# Relay.net
KiCad netlist of a schematic drawn in EAGLE
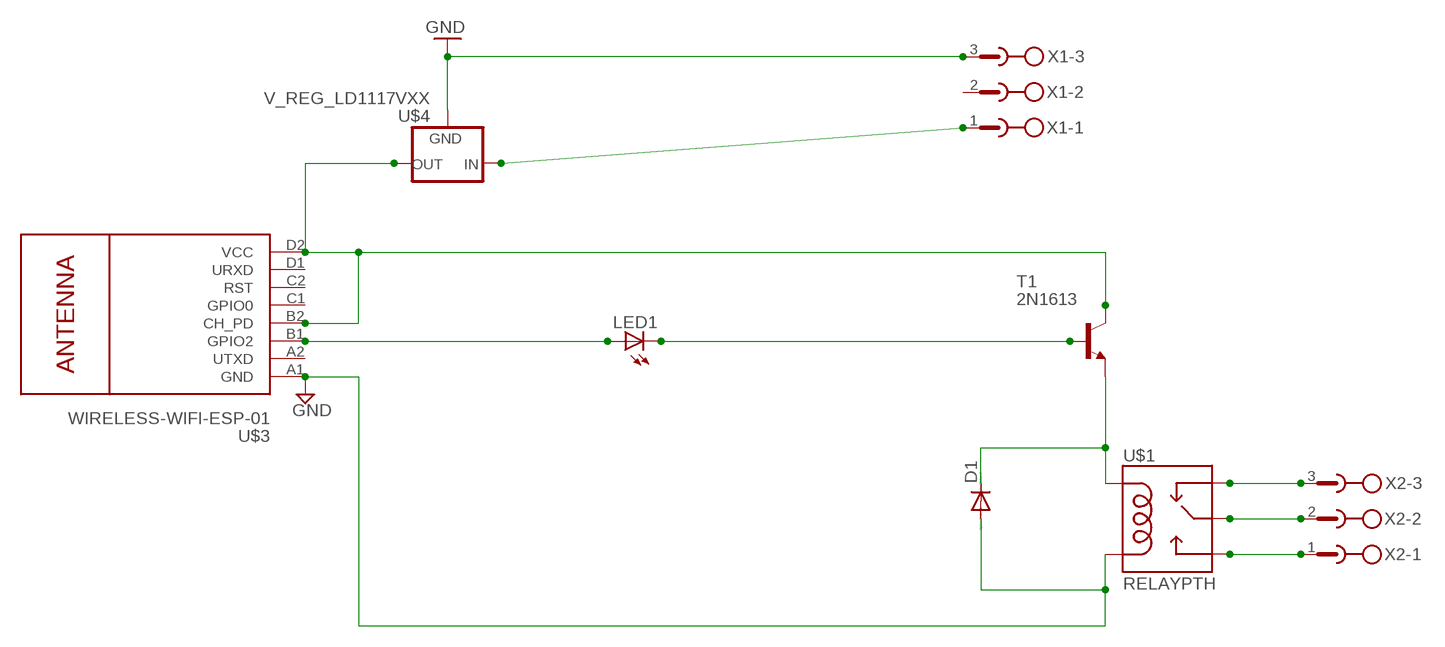
[diagram p0: schematic, sheet 1]

(export (version "E")
  (design (tool "Eeschema 10.0.6"))
  (components
    (comp (ref "D1")
      (value "DIODE-D-2.5")
      (footprint "eagle-import:D-2.5")
      (libsource (lib "eagle-import") (part "DIODE-D-2.5"))
    )
    (comp (ref "LED1")
      (value "LED3MM")
      (footprint "eagle-import:LED3MM")
      (libsource (lib "eagle-import") (part "LED3MM"))
    )
    (comp (ref "T1")
      (value "2N1613")
      (footprint "eagle-import:TO5")
      (libsource (lib "eagle-import") (part "2N1613"))
    )
    (comp (ref "U$1")
      (value "RELAYPTH")
      (footprint "eagle-import:SRD-05VDC-SL-C")
      (libsource (lib "eagle-import") (part "RELAYPTH"))
    )
    (comp (ref "U$3")
      (value "WIRELESS-WIFI-ESP-01")
      (footprint "eagle-import:WIRELESS-WIFI-ESP-01")
      (libsource (lib "eagle-import") (part "WIRELESS-WIFI-ESP-01"))
    )
    (comp (ref "U$4")
      (value "V_REG_LD1117VXX")
      (footprint "eagle-import:78XXL")
      (libsource (lib "eagle-import") (part "V_REG_LD1117VXX"))
    )
    (comp (ref "X1")
      (value "W232-3")
      (footprint "eagle-import:W232-3")
      (libsource (lib "eagle-import") (part "W232-3"))
    )
    (comp (ref "X2")
      (value "W232-3")
      (footprint "eagle-import:W232-3")
      (libsource (lib "eagle-import") (part "W232-3"))
    )
  )
  (nets
    (net (code "1") (name "GND") (class "Default")
      (node (ref "D1") (pin "A") (pinfunction "A_A") (pintype "passive"))
      (node (ref "U$1") (pin "COIL0") (pinfunction "COIL0_COIL0") (pintype "bidirectional"))
      (node (ref "U$3") (pin "A1") (pinfunction "GND_A1") (pintype "power_in"))
      (node (ref "U$4") (pin "IN") (pinfunction "GND_IN") (pintype "input"))
      (node (ref "X1") (pin "3") (pinfunction "SK_3") (pintype "passive"))
    )
    (net (code "2") (name "Net-(LED1-C)") (class "Default")
      (node (ref "LED1") (pin "K") (pinfunction "C_K") (pintype "passive"))
      (node (ref "T1") (pin "2") (pinfunction "B_2") (pintype "passive"))
    )
    (net (code "3") (name "Net-(T1-C)") (class "Default")
      (node (ref "T1") (pin "3") (pinfunction "C_3") (pintype "passive"))
      (node (ref "U$3") (pin "B2") (pinfunction "CH_PD_B2") (pintype "bidirectional"))
      (node (ref "U$3") (pin "D2") (pinfunction "VCC_D2") (pintype "power_in"))
      (node (ref "U$4") (pin "GND") (pinfunction "OUT_GND") (pintype "passive"))
    )
    (net (code "4") (name "Net-(T1-E)") (class "Default")
      (node (ref "D1") (pin "C") (pinfunction "C_C") (pintype "passive"))
      (node (ref "T1") (pin "1") (pinfunction "E_1") (pintype "passive"))
      (node (ref "U$1") (pin "COIL1") (pinfunction "COIL1_COIL1") (pintype "bidirectional"))
    )
    (net (code "5") (name "Net-(U$1-SWCLOSE)") (class "Default")
      (node (ref "U$1") (pin "SWCLOSED") (pinfunction "SWCLOSE_SWCLOSED") (pintype "bidirectional"))
      (node (ref "X2") (pin "3") (pinfunction "SK_3") (pintype "passive"))
    )
    (net (code "6") (name "Net-(U$3-GPIO2)") (class "Default")
      (node (ref "LED1") (pin "A") (pinfunction "A_A") (pintype "passive"))
      (node (ref "U$3") (pin "B1") (pinfunction "GPIO2_B1") (pintype "bidirectional"))
    )
    (net (code "7") (name "Net-(U$4-IN)") (class "Default")
      (node (ref "U$4") (pin "OUT") (pinfunction "IN_OUT") (pintype "input"))
      (node (ref "X1") (pin "1") (pinfunction "SK_1") (pintype "passive"))
    )
    (net (code "8") (name "Net-(X2A-SK)") (class "Default")
      (node (ref "U$1") (pin "SWOPEN") (pinfunction "SWOPEN_SWOPEN") (pintype "bidirectional"))
      (node (ref "X2") (pin "1") (pinfunction "SK_1") (pintype "passive"))
    )
    (net (code "9") (name "Net-(X2B-SK)") (class "Default")
      (node (ref "U$1") (pin "SWCOMMON") (pinfunction "SWCOMMON_SWCOMMON") (pintype "bidirectional"))
      (node (ref "X2") (pin "2") (pinfunction "SK_2") (pintype "passive"))
    )
    (net (code "10") (name "unconnected-(U$3-GPIO0-PadC1)") (class "Default")
      (node (ref "U$3") (pin "C1") (pinfunction "GPIO0_C1") (pintype "bidirectional"))
    )
    (net (code "11") (name "unconnected-(U$3-RST-PadC2)") (class "Default")
      (node (ref "U$3") (pin "C2") (pinfunction "RST_C2") (pintype "bidirectional"))
    )
    (net (code "12") (name "unconnected-(U$3-URXD-PadD1)") (class "Default")
      (node (ref "U$3") (pin "D1") (pinfunction "URXD_D1") (pintype "bidirectional"))
    )
    (net (code "13") (name "unconnected-(U$3-UTXD-PadA2)") (class "Default")
      (node (ref "U$3") (pin "A2") (pinfunction "UTXD_A2") (pintype "bidirectional"))
    )
    (net (code "14") (name "unconnected-(X1B-SK-Pad2)") (class "Default")
      (node (ref "X1") (pin "2") (pinfunction "SK_2") (pintype "passive"))
    )
  )
)
